# ECHO_RECEIVER.net
KiCad netlist of a schematic drawn in EasyEDA Pro
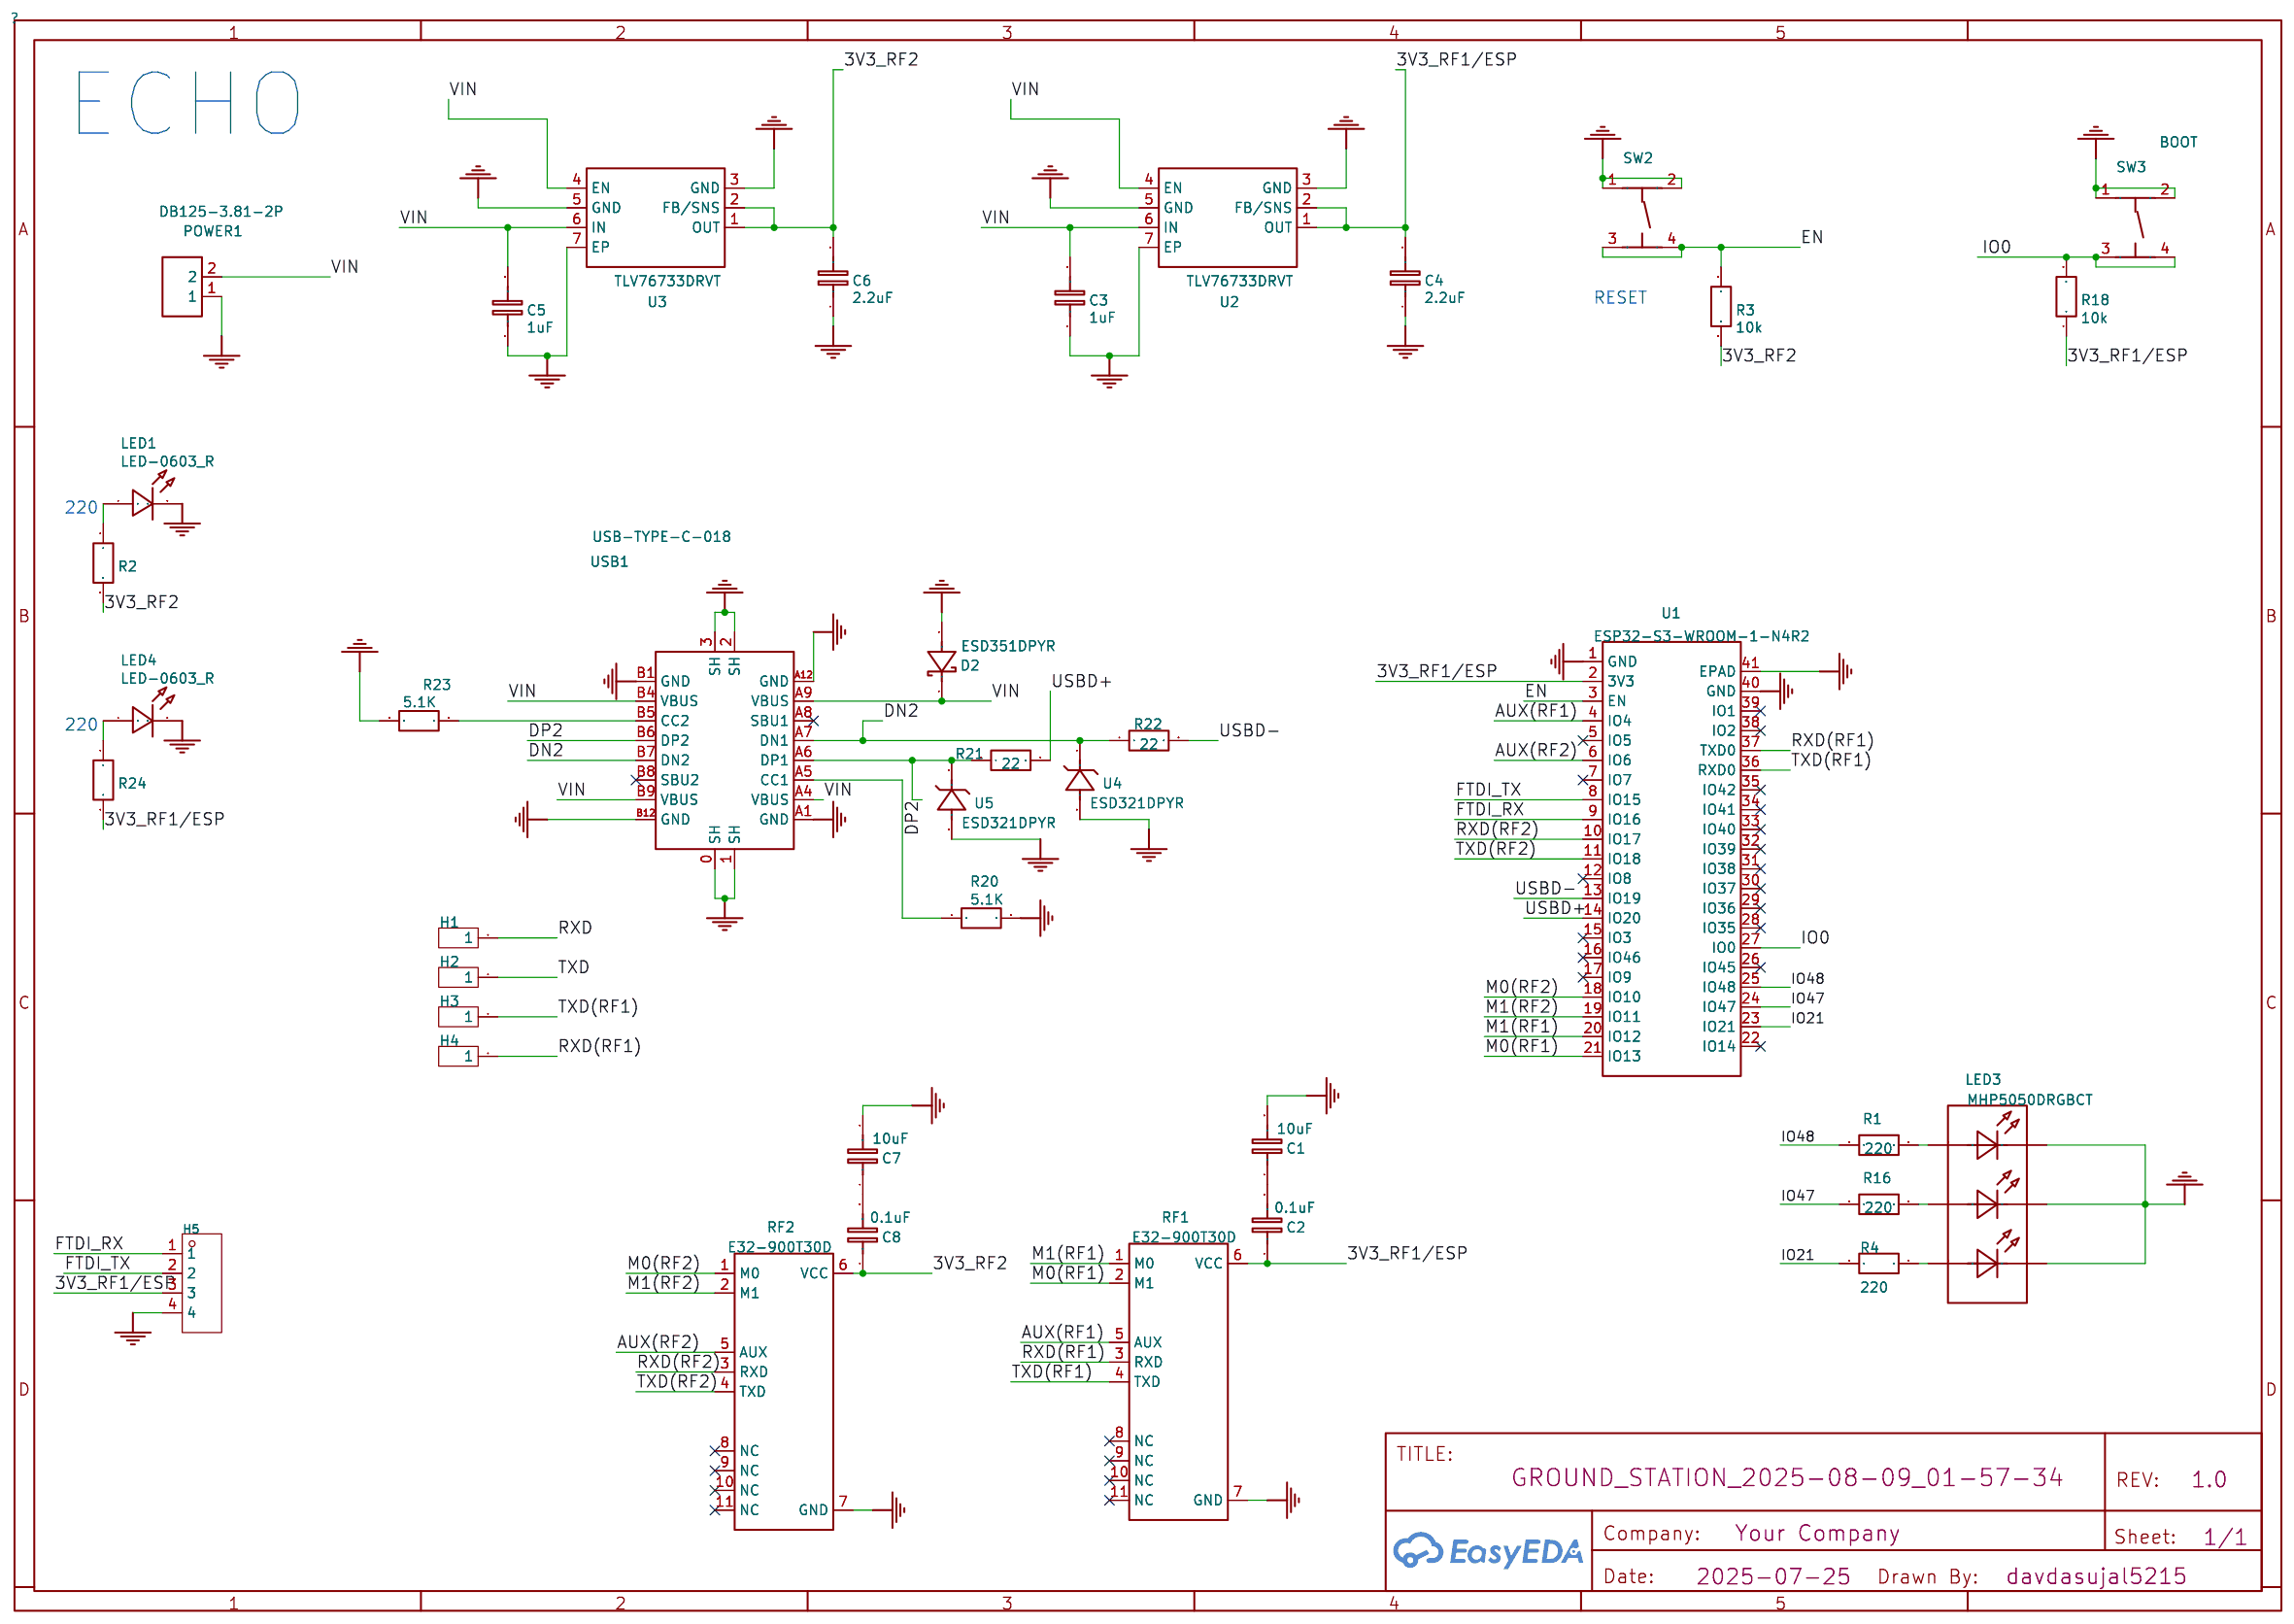
[diagram p0: schematic sheet]

(export (version "E")
  (design (tool "Eeschema 10.0.6"))
  (components
    (comp (ref "C1")
      (value "10uF")
      (footprint "easyedapro:C0603")
      (fields (field (name "Contributor") "LCEDA_Lib"))
      (libsource (lib "easyedapro") (part "10uF"))
    )
    (comp (ref "C2")
      (value "0.1uF")
      (footprint "easyedapro:C0603")
      (fields (field (name "Contributor") "LCEDA_Lib"))
      (libsource (lib "easyedapro") (part "0.1uF"))
    )
    (comp (ref "C3")
      (value "1uF")
      (footprint "easyedapro:C0603")
      (fields (field (name "Contributor") "LCEDA_Lib"))
      (libsource (lib "easyedapro") (part "1uF"))
    )
    (comp (ref "C4")
      (value "2.2uF")
      (footprint "easyedapro:C0603")
      (fields (field (name "Contributor") "LCEDA_Lib"))
      (libsource (lib "easyedapro") (part "2.2uF"))
    )
    (comp (ref "C5")
      (value "1uF")
      (footprint "easyedapro:C0603")
      (fields (field (name "Contributor") "LCEDA_Lib"))
      (libsource (lib "easyedapro") (part "1uF"))
    )
    (comp (ref "C6")
      (value "2.2uF")
      (footprint "easyedapro:C0603")
      (fields (field (name "Contributor") "LCEDA_Lib"))
      (libsource (lib "easyedapro") (part "2.2uF"))
    )
    (comp (ref "C7")
      (value "10uF")
      (footprint "easyedapro:C0603")
      (fields (field (name "Contributor") "LCEDA_Lib"))
      (libsource (lib "easyedapro") (part "10uF"))
    )
    (comp (ref "C8")
      (value "0.1uF")
      (footprint "easyedapro:C0603")
      (fields (field (name "Contributor") "LCEDA_Lib"))
      (libsource (lib "easyedapro") (part "0.1uF"))
    )
    (comp (ref "D2")
      (value "ESD351DPYR")
      (footprint "easyedapro:X1SON-2_L1.0-W0.6-P0.65-RD-1")
      (fields (field (name "Manufacturer") "TI(德州仪器)") (field (name "Contributor") "LCSC"))
      (libsource (lib "easyedapro") (part "ESD351DPYR"))
    )
    (comp (ref "H1")
      (value "~")
      (footprint "easyedapro:HDR-TH_1P-V-M_XKB_X4611WV-01I-C28D40")
      (libsource (lib "easyedapro") (part "HDR_1x1"))
    )
    (comp (ref "H2")
      (value "~")
      (footprint "easyedapro:HDR-TH_1P-V-M_XKB_X4611WV-01I-C28D40")
      (libsource (lib "easyedapro") (part "HDR_1x1"))
    )
    (comp (ref "H3")
      (value "~")
      (footprint "easyedapro:HDR-TH_1P-V-M_XKB_X4611WV-01I-C28D40")
      (libsource (lib "easyedapro") (part "HDR_1x1"))
    )
    (comp (ref "H4")
      (value "~")
      (footprint "easyedapro:HDR-TH_1P-V-M_XKB_X4611WV-01I-C28D40")
      (libsource (lib "easyedapro") (part "HDR_1x1"))
    )
    (comp (ref "H5")
      (value "~")
      (footprint "easyedapro:HDR-TH_4P-P2.54-V-F")
      (libsource (lib "easyedapro") (part "2.54-1*4P母"))
    )
    (comp (ref "LED1")
      (value "LED-0603_R")
      (footprint "easyedapro:LED0603_RED")
      (fields
        (field (name "Manufacturer Part") "19-217/R6C-AL1M2VY/3T")
        (field (name "Manufacturer") "EVERLIGHT(台湾亿光)")
        (field (name "Contributor") "LCEDA_01")
      )
      (libsource (lib "easyedapro") (part "LED-0603_R"))
    )
    (comp (ref "LED3")
      (value "MHP5050DRGBCT")
      (footprint "easyedapro:LED-SMD_6P-L5.0-W5.0-P1.60-LS4.4-TL_MHP5050DRGBCT")
      (fields (field (name "Manufacturer") "MEIHUA(美华)") (field (name "Contributor") "lcsc"))
      (libsource (lib "easyedapro") (part "MHP5050DRGBCT"))
    )
    (comp (ref "LED4")
      (value "LED-0603_R")
      (footprint "easyedapro:LED0603_RED")
      (fields
        (field (name "Manufacturer Part") "19-217/R6C-AL1M2VY/3T")
        (field (name "Manufacturer") "EVERLIGHT(台湾亿光)")
        (field (name "Contributor") "LCEDA_01")
      )
      (libsource (lib "easyedapro") (part "LED-0603_R"))
    )
    (comp (ref "POWER1")
      (value "DB125-3.81-2P")
      (footprint "easyedapro:CONN-TH_2P-P3.81_L7.4-W7.6")
      (fields
        (field (name "Manufacturer Part") "DB125-3.81-2P-GN-S")
        (field (name "Manufacturer") "DORABO(地博电气)")
        (field (name "Contributor") "LCSC")
      )
      (libsource (lib "easyedapro") (part "DB125-3.81-2P"))
    )
    (comp (ref "R1")
      (value "220")
      (footprint "easyedapro:R0603")
      (fields (field (name "Contributor") "LCEDA_Lib"))
      (libsource (lib "easyedapro") (part "220"))
    )
    (comp (ref "R2")
      (value "10k")
      (footprint "easyedapro:R0603")
      (fields (field (name "Contributor") "LCEDA_Lib"))
      (libsource (lib "easyedapro") (part "10k"))
    )
    (comp (ref "R3")
      (value "10k")
      (footprint "easyedapro:R0603")
      (fields (field (name "Contributor") "LCEDA_Lib"))
      (libsource (lib "easyedapro") (part "10k"))
    )
    (comp (ref "R4")
      (value "220")
      (footprint "easyedapro:R0603")
      (fields (field (name "Contributor") "LCEDA_Lib"))
      (libsource (lib "") (part "220_1"))
    )
    (comp (ref "R16")
      (value "220")
      (footprint "easyedapro:R0603")
      (fields (field (name "Contributor") "LCEDA_Lib"))
      (libsource (lib "easyedapro") (part "220"))
    )
    (comp (ref "R18")
      (value "10k")
      (footprint "easyedapro:R0603")
      (fields (field (name "Contributor") "LCEDA_Lib"))
      (libsource (lib "") (part "10k_1"))
    )
    (comp (ref "R20")
      (value "5.1K")
      (footprint "easyedapro:R0603")
      (fields (field (name "Contributor") "LCEDA_Lib"))
      (libsource (lib "easyedapro") (part "5.1K"))
    )
    (comp (ref "R21")
      (value "22")
      (footprint "easyedapro:R0603")
      (fields (field (name "Contributor") "LCEDA_Lib"))
      (libsource (lib "easyedapro") (part "22"))
    )
    (comp (ref "R22")
      (value "22")
      (footprint "easyedapro:R0603")
      (fields (field (name "Contributor") "LCEDA_Lib"))
      (libsource (lib "easyedapro") (part "22"))
    )
    (comp (ref "R23")
      (value "5.1K")
      (footprint "easyedapro:R0603")
      (fields (field (name "Contributor") "LCEDA_Lib"))
      (libsource (lib "") (part "5.1K_1"))
    )
    (comp (ref "R24")
      (value "10k")
      (footprint "easyedapro:R0603")
      (fields (field (name "Contributor") "LCEDA_Lib"))
      (libsource (lib "easyedapro") (part "10k"))
    )
    (comp (ref "RF1")
      (value "E32-900T30D")
      (footprint "easyedapro:WIRELM-TH_E32-900T30D")
      (fields (field (name "Contributor") "lcsc"))
      (libsource (lib "easyedapro") (part "E32-900T30D"))
    )
    (comp (ref "RF2")
      (value "E32-900T30D")
      (footprint "easyedapro:WIRELM-TH_E32-900T30D")
      (fields (field (name "Contributor") "lcsc"))
      (libsource (lib "easyedapro") (part "E32-900T30D"))
    )
    (comp (ref "SW2")
      (value "RESET")
      (footprint "easyedapro:SW-SMD_4P-L4.5-W4.5-P3.00-LS7.0")
      (fields
        (field (name "Manufacturer Part") "TS-1109S-C-A")
        (field (name "Manufacturer") "XKB Enterprise")
        (field (name "Contributor") "Igor Iks")
      )
      (libsource (lib "easyedapro") (part "RESET"))
    )
    (comp (ref "SW3")
      (value "BOOT")
      (footprint "easyedapro:SW-SMD_4P-L4.5-W4.5-P3.00-LS7.0")
      (fields
        (field (name "Manufacturer Part") "TS-1109S-C-A")
        (field (name "Manufacturer") "XKB Enterprise")
        (field (name "Contributor") "Igor Iks")
      )
      (libsource (lib "easyedapro") (part "BOOT"))
    )
    (comp (ref "U1")
      (value "ESP32-S3-WROOM-1-N4R2")
      (footprint "easyedapro:WIRELM-SMD_ESP32-S3-WROOM-1")
      (fields (field (name "Manufacturer") "ESPRESSIF(乐鑫)") (field (name "Contributor") "lcsc"))
      (libsource (lib "easyedapro") (part "ESP32-S3-WROOM-1-N4R2"))
    )
    (comp (ref "U2")
      (value "TLV76733DRVT")
      (footprint "easyedapro:WSON-6_L2.0-W2.0-P0.65-TL-EP")
      (fields (field (name "Manufacturer") "TI(德州仪器)") (field (name "Contributor") "LCSC"))
      (libsource (lib "easyedapro") (part "TLV76733DRVT"))
    )
    (comp (ref "U3")
      (value "TLV76733DRVT")
      (footprint "easyedapro:WSON-6_L2.0-W2.0-P0.65-TL-EP")
      (fields (field (name "Manufacturer") "TI(德州仪器)") (field (name "Contributor") "LCSC"))
      (libsource (lib "easyedapro") (part "TLV76733DRVT"))
    )
    (comp (ref "U4")
      (value "ESD321DPYR")
      (footprint "easyedapro:X1SON-2_L1.0-W0.6-P0.65-RD")
      (fields (field (name "Contributor") "LCSC"))
      (libsource (lib "easyedapro") (part "ESD321DPYR"))
    )
    (comp (ref "U5")
      (value "ESD321DPYR")
      (footprint "easyedapro:X1SON-2_L1.0-W0.6-P0.65-RD")
      (fields (field (name "Contributor") "LCSC"))
      (libsource (lib "easyedapro") (part "ESD321DPYR"))
    )
    (comp (ref "USB1")
      (value "USB-TYPE-C-018")
      (footprint "easyedapro:USB-C_SMD-TYPE-C-31-M-12")
      (fields (field (name "Manufacturer") "DEALON(德艺隆)") (field (name "Contributor") "LCSC"))
      (libsource (lib "easyedapro") (part "USB-TYPE-C-018"))
    )
  )
  (nets
    (net (code "1") (name "/3V3_RF1{slash}ESP") (class "Default")
      (node (ref "C2") (pin "1") (pinfunction "1_1") (pintype "unspecified"))
      (node (ref "C4") (pin "2") (pinfunction "2_2") (pintype "unspecified"))
      (node (ref "H5") (pin "3") (pinfunction "3_3") (pintype "input"))
      (node (ref "R18") (pin "1") (pinfunction "1_1") (pintype "unspecified"))
      (node (ref "R24") (pin "2") (pinfunction "2_2") (pintype "unspecified"))
      (node (ref "RF1") (pin "6") (pinfunction "VCC_6") (pintype "unspecified"))
      (node (ref "U1") (pin "2") (pinfunction "3V3_2") (pintype "unspecified"))
      (node (ref "U2") (pin "1") (pinfunction "OUT_1") (pintype "unspecified"))
      (node (ref "U2") (pin "2") (pinfunction "FB/SNS_2") (pintype "unspecified"))
    )
    (net (code "2") (name "/3V3_RF2") (class "Default")
      (node (ref "C6") (pin "2") (pinfunction "2_2") (pintype "unspecified"))
      (node (ref "C8") (pin "1") (pinfunction "1_1") (pintype "unspecified"))
      (node (ref "R2") (pin "2") (pinfunction "2_2") (pintype "unspecified"))
      (node (ref "R3") (pin "2") (pinfunction "2_2") (pintype "unspecified"))
      (node (ref "RF2") (pin "6") (pinfunction "VCC_6") (pintype "unspecified"))
      (node (ref "U3") (pin "1") (pinfunction "OUT_1") (pintype "unspecified"))
      (node (ref "U3") (pin "2") (pinfunction "FB/SNS_2") (pintype "unspecified"))
    )
    (net (code "3") (name "/AUX(RF1)") (class "Default")
      (node (ref "RF1") (pin "5") (pinfunction "AUX_5") (pintype "unspecified"))
      (node (ref "U1") (pin "4") (pinfunction "IO4_4") (pintype "unspecified"))
    )
    (net (code "4") (name "/AUX(RF2)") (class "Default")
      (node (ref "RF2") (pin "5") (pinfunction "AUX_5") (pintype "unspecified"))
      (node (ref "U1") (pin "6") (pinfunction "IO6_6") (pintype "unspecified"))
    )
    (net (code "5") (name "/DN2") (class "Default")
      (node (ref "R22") (pin "1") (pinfunction "1_1") (pintype "unspecified"))
      (node (ref "U4") (pin "1") (pinfunction "K_1") (pintype "unspecified"))
      (node (ref "USB1") (pin "A7") (pinfunction "DN1_A7") (pintype "unspecified"))
      (node (ref "USB1") (pin "B7") (pinfunction "DN2_B7") (pintype "unspecified"))
    )
    (net (code "6") (name "/DP2") (class "Default")
      (node (ref "R21") (pin "1") (pinfunction "1_1") (pintype "unspecified"))
      (node (ref "U5") (pin "1") (pinfunction "K_1") (pintype "unspecified"))
      (node (ref "USB1") (pin "A6") (pinfunction "DP1_A6") (pintype "unspecified"))
      (node (ref "USB1") (pin "B6") (pinfunction "DP2_B6") (pintype "unspecified"))
    )
    (net (code "7") (name "/EN") (class "Default")
      (node (ref "R3") (pin "1") (pinfunction "1_1") (pintype "unspecified"))
      (node (ref "SW2") (pin "3") (pinfunction "3_3") (pintype "unspecified"))
      (node (ref "SW2") (pin "4") (pinfunction "4_4") (pintype "unspecified"))
      (node (ref "U1") (pin "3") (pinfunction "EN_3") (pintype "unspecified"))
    )
    (net (code "8") (name "/FTDI_RX") (class "Default")
      (node (ref "H5") (pin "1") (pinfunction "1_1") (pintype "input"))
      (node (ref "U1") (pin "9") (pinfunction "IO16_9") (pintype "unspecified"))
    )
    (net (code "9") (name "/FTDI_TX") (class "Default")
      (node (ref "H5") (pin "2") (pinfunction "2_2") (pintype "input"))
      (node (ref "U1") (pin "8") (pinfunction "IO15_8") (pintype "unspecified"))
    )
    (net (code "10") (name "/IO0") (class "Default")
      (node (ref "R18") (pin "2") (pinfunction "2_2") (pintype "unspecified"))
      (node (ref "SW3") (pin "3") (pinfunction "3_3") (pintype "unspecified"))
      (node (ref "SW3") (pin "4") (pinfunction "4_4") (pintype "unspecified"))
      (node (ref "U1") (pin "27") (pinfunction "IO0_27") (pintype "unspecified"))
    )
    (net (code "11") (name "/IO21") (class "Default")
      (node (ref "R4") (pin "2") (pinfunction "2_2") (pintype "unspecified"))
      (node (ref "U1") (pin "23") (pinfunction "IO21_23") (pintype "unspecified"))
    )
    (net (code "12") (name "/IO47") (class "Default")
      (node (ref "R16") (pin "1") (pinfunction "1_1") (pintype "unspecified"))
      (node (ref "U1") (pin "24") (pinfunction "IO47_24") (pintype "unspecified"))
    )
    (net (code "13") (name "/IO48") (class "Default")
      (node (ref "R1") (pin "1") (pinfunction "1_1") (pintype "unspecified"))
      (node (ref "U1") (pin "25") (pinfunction "IO48_25") (pintype "unspecified"))
    )
    (net (code "14") (name "/M0(RF1)") (class "Default")
      (node (ref "RF1") (pin "2") (pinfunction "M1_2") (pintype "unspecified"))
      (node (ref "U1") (pin "21") (pinfunction "IO13_21") (pintype "unspecified"))
    )
    (net (code "15") (name "/M0(RF2)") (class "Default")
      (node (ref "RF2") (pin "1") (pinfunction "M0_1") (pintype "unspecified"))
      (node (ref "U1") (pin "18") (pinfunction "IO10_18") (pintype "unspecified"))
    )
    (net (code "16") (name "/M1(RF1)") (class "Default")
      (node (ref "RF1") (pin "1") (pinfunction "M0_1") (pintype "unspecified"))
      (node (ref "U1") (pin "20") (pinfunction "IO12_20") (pintype "unspecified"))
    )
    (net (code "17") (name "/M1(RF2)") (class "Default")
      (node (ref "RF2") (pin "2") (pinfunction "M1_2") (pintype "unspecified"))
      (node (ref "U1") (pin "19") (pinfunction "IO11_19") (pintype "unspecified"))
    )
    (net (code "18") (name "/RXD") (class "Default")
      (node (ref "H1") (pin "1") (pinfunction "1_1") (pintype "unspecified"))
    )
    (net (code "19") (name "/RXD(RF1)") (class "Default")
      (node (ref "H4") (pin "1") (pinfunction "1_1") (pintype "unspecified"))
      (node (ref "RF1") (pin "3") (pinfunction "RXD_3") (pintype "unspecified"))
      (node (ref "U1") (pin "37") (pinfunction "TXD0_37") (pintype "unspecified"))
    )
    (net (code "20") (name "/RXD(RF2)") (class "Default")
      (node (ref "RF2") (pin "3") (pinfunction "RXD_3") (pintype "unspecified"))
      (node (ref "U1") (pin "10") (pinfunction "IO17_10") (pintype "unspecified"))
    )
    (net (code "21") (name "/TXD") (class "Default")
      (node (ref "H2") (pin "1") (pinfunction "1_1") (pintype "unspecified"))
    )
    (net (code "22") (name "/TXD(RF1)") (class "Default")
      (node (ref "H3") (pin "1") (pinfunction "1_1") (pintype "unspecified"))
      (node (ref "RF1") (pin "4") (pinfunction "TXD_4") (pintype "unspecified"))
      (node (ref "U1") (pin "36") (pinfunction "RXD0_36") (pintype "unspecified"))
    )
    (net (code "23") (name "/TXD(RF2)") (class "Default")
      (node (ref "RF2") (pin "4") (pinfunction "TXD_4") (pintype "unspecified"))
      (node (ref "U1") (pin "11") (pinfunction "IO18_11") (pintype "unspecified"))
    )
    (net (code "24") (name "/USBD+") (class "Default")
      (node (ref "R21") (pin "2") (pinfunction "2_2") (pintype "unspecified"))
      (node (ref "U1") (pin "14") (pinfunction "IO20_14") (pintype "unspecified"))
    )
    (net (code "25") (name "/USBD-") (class "Default")
      (node (ref "R22") (pin "2") (pinfunction "2_2") (pintype "unspecified"))
      (node (ref "U1") (pin "13") (pinfunction "IO19_13") (pintype "unspecified"))
    )
    (net (code "26") (name "/VIN") (class "Default")
      (node (ref "C3") (pin "2") (pinfunction "2_2") (pintype "unspecified"))
      (node (ref "C5") (pin "2") (pinfunction "2_2") (pintype "unspecified"))
      (node (ref "D2") (pin "1") (pinfunction "K_1") (pintype "unspecified"))
      (node (ref "POWER1") (pin "2") (pinfunction "2_2") (pintype "unspecified"))
      (node (ref "U2") (pin "4") (pinfunction "EN_4") (pintype "unspecified"))
      (node (ref "U2") (pin "6") (pinfunction "IN_6") (pintype "unspecified"))
      (node (ref "U3") (pin "4") (pinfunction "EN_4") (pintype "unspecified"))
      (node (ref "U3") (pin "6") (pinfunction "IN_6") (pintype "unspecified"))
      (node (ref "USB1") (pin "A4") (pinfunction "VBUS_A4") (pintype "unspecified"))
      (node (ref "USB1") (pin "A9") (pinfunction "VBUS_A9") (pintype "unspecified"))
      (node (ref "USB1") (pin "B4") (pinfunction "VBUS_B4") (pintype "unspecified"))
      (node (ref "USB1") (pin "B9") (pinfunction "VBUS_B9") (pintype "unspecified"))
    )
    (net (code "27") (name "GND") (class "Default")
      (node (ref "C1") (pin "2") (pinfunction "2_2") (pintype "unspecified"))
      (node (ref "C3") (pin "1") (pinfunction "1_1") (pintype "unspecified"))
      (node (ref "C4") (pin "1") (pinfunction "1_1") (pintype "unspecified"))
      (node (ref "C5") (pin "1") (pinfunction "1_1") (pintype "unspecified"))
      (node (ref "C6") (pin "1") (pinfunction "1_1") (pintype "unspecified"))
      (node (ref "C7") (pin "2") (pinfunction "2_2") (pintype "unspecified"))
      (node (ref "D2") (pin "2") (pinfunction "A_2") (pintype "unspecified"))
      (node (ref "H5") (pin "4") (pinfunction "4_4") (pintype "input"))
      (node (ref "LED1") (pin "2") (pinfunction "2_2") (pintype "unspecified"))
      (node (ref "LED3") (pin "4") (pinfunction "B-_4") (pintype "unspecified"))
      (node (ref "LED3") (pin "5") (pinfunction "R-_5") (pintype "unspecified"))
      (node (ref "LED3") (pin "6") (pinfunction "G-_6") (pintype "unspecified"))
      (node (ref "LED4") (pin "2") (pinfunction "2_2") (pintype "unspecified"))
      (node (ref "POWER1") (pin "1") (pinfunction "1_1") (pintype "unspecified"))
      (node (ref "R20") (pin "2") (pinfunction "2_2") (pintype "unspecified"))
      (node (ref "R23") (pin "2") (pinfunction "2_2") (pintype "unspecified"))
      (node (ref "RF1") (pin "7") (pinfunction "GND_7") (pintype "unspecified"))
      (node (ref "RF2") (pin "7") (pinfunction "GND_7") (pintype "unspecified"))
      (node (ref "SW2") (pin "1") (pinfunction "1_1") (pintype "unspecified"))
      (node (ref "SW2") (pin "2") (pinfunction "2_2") (pintype "unspecified"))
      (node (ref "SW3") (pin "1") (pinfunction "1_1") (pintype "unspecified"))
      (node (ref "SW3") (pin "2") (pinfunction "2_2") (pintype "unspecified"))
      (node (ref "U1") (pin "1") (pinfunction "GND_1") (pintype "unspecified"))
      (node (ref "U1") (pin "40") (pinfunction "GND_40") (pintype "unspecified"))
      (node (ref "U1") (pin "41") (pinfunction "EPAD_41") (pintype "unspecified"))
      (node (ref "U2") (pin "3") (pinfunction "GND_3") (pintype "unspecified"))
      (node (ref "U2") (pin "5") (pinfunction "GND_5") (pintype "unspecified"))
      (node (ref "U2") (pin "7") (pinfunction "EP_7") (pintype "unspecified"))
      (node (ref "U3") (pin "3") (pinfunction "GND_3") (pintype "unspecified"))
      (node (ref "U3") (pin "5") (pinfunction "GND_5") (pintype "unspecified"))
      (node (ref "U3") (pin "7") (pinfunction "EP_7") (pintype "unspecified"))
      (node (ref "U4") (pin "2") (pinfunction "A_2") (pintype "unspecified"))
      (node (ref "U5") (pin "2") (pinfunction "A_2") (pintype "unspecified"))
      (node (ref "USB1") (pin "0") (pinfunction "SH_0") (pintype "unspecified"))
      (node (ref "USB1") (pin "1") (pinfunction "SH_1") (pintype "unspecified"))
      (node (ref "USB1") (pin "2") (pinfunction "SH_2") (pintype "unspecified"))
      (node (ref "USB1") (pin "3") (pinfunction "SH_3") (pintype "unspecified"))
      (node (ref "USB1") (pin "A1") (pinfunction "GND_A1") (pintype "unspecified"))
      (node (ref "USB1") (pin "A12") (pinfunction "GND_A12") (pintype "unspecified"))
      (node (ref "USB1") (pin "B1") (pinfunction "GND_B1") (pintype "unspecified"))
      (node (ref "USB1") (pin "B12") (pinfunction "GND_B12") (pintype "unspecified"))
    )
    (net (code "28") (name "Net-(C1-Pad1)") (class "Default")
      (node (ref "C1") (pin "1") (pinfunction "1_1") (pintype "unspecified"))
      (node (ref "C2") (pin "2") (pinfunction "2_2") (pintype "unspecified"))
    )
    (net (code "29") (name "Net-(C7-Pad1)") (class "Default")
      (node (ref "C7") (pin "1") (pinfunction "1_1") (pintype "unspecified"))
      (node (ref "C8") (pin "2") (pinfunction "2_2") (pintype "unspecified"))
    )
    (net (code "30") (name "Net-(LED1-Pad1)") (class "Default")
      (node (ref "LED1") (pin "1") (pinfunction "1_1") (pintype "unspecified"))
      (node (ref "R2") (pin "1") (pinfunction "1_1") (pintype "unspecified"))
    )
    (net (code "31") (name "Net-(LED3-B+)") (class "Default")
      (node (ref "LED3") (pin "3") (pinfunction "B+_3") (pintype "unspecified"))
      (node (ref "R4") (pin "1") (pinfunction "1_1") (pintype "unspecified"))
    )
    (net (code "32") (name "Net-(LED3-G+)") (class "Default")
      (node (ref "LED3") (pin "1") (pinfunction "G+_1") (pintype "unspecified"))
      (node (ref "R1") (pin "2") (pinfunction "2_2") (pintype "unspecified"))
    )
    (net (code "33") (name "Net-(LED3-R+)") (class "Default")
      (node (ref "LED3") (pin "2") (pinfunction "R+_2") (pintype "unspecified"))
      (node (ref "R16") (pin "2") (pinfunction "2_2") (pintype "unspecified"))
    )
    (net (code "34") (name "Net-(LED4-Pad1)") (class "Default")
      (node (ref "LED4") (pin "1") (pinfunction "1_1") (pintype "unspecified"))
      (node (ref "R24") (pin "1") (pinfunction "1_1") (pintype "unspecified"))
    )
    (net (code "35") (name "Net-(USB1-CC1)") (class "Default")
      (node (ref "R20") (pin "1") (pinfunction "1_1") (pintype "unspecified"))
      (node (ref "USB1") (pin "A5") (pinfunction "CC1_A5") (pintype "unspecified"))
    )
    (net (code "36") (name "Net-(USB1-CC2)") (class "Default")
      (node (ref "R23") (pin "1") (pinfunction "1_1") (pintype "unspecified"))
      (node (ref "USB1") (pin "B5") (pinfunction "CC2_B5") (pintype "unspecified"))
    )
    (net (code "37") (name "unconnected-(RF1-NC-Pad8)") (class "Default")
      (node (ref "RF1") (pin "8") (pinfunction "NC_8") (pintype "unspecified+no_connect"))
    )
    (net (code "38") (name "unconnected-(RF1-NC-Pad9)") (class "Default")
      (node (ref "RF1") (pin "9") (pinfunction "NC_9") (pintype "unspecified+no_connect"))
    )
    (net (code "39") (name "unconnected-(RF1-NC-Pad10)") (class "Default")
      (node (ref "RF1") (pin "10") (pinfunction "NC_10") (pintype "unspecified+no_connect"))
    )
    (net (code "40") (name "unconnected-(RF1-NC-Pad11)") (class "Default")
      (node (ref "RF1") (pin "11") (pinfunction "NC_11") (pintype "unspecified+no_connect"))
    )
    (net (code "41") (name "unconnected-(RF2-NC-Pad8)") (class "Default")
      (node (ref "RF2") (pin "8") (pinfunction "NC_8") (pintype "unspecified+no_connect"))
    )
    (net (code "42") (name "unconnected-(RF2-NC-Pad9)") (class "Default")
      (node (ref "RF2") (pin "9") (pinfunction "NC_9") (pintype "unspecified+no_connect"))
    )
    (net (code "43") (name "unconnected-(RF2-NC-Pad10)") (class "Default")
      (node (ref "RF2") (pin "10") (pinfunction "NC_10") (pintype "unspecified+no_connect"))
    )
    (net (code "44") (name "unconnected-(RF2-NC-Pad11)") (class "Default")
      (node (ref "RF2") (pin "11") (pinfunction "NC_11") (pintype "unspecified+no_connect"))
    )
    (net (code "45") (name "unconnected-(U1-IO1-Pad39)") (class "Default")
      (node (ref "U1") (pin "39") (pinfunction "IO1_39") (pintype "unspecified+no_connect"))
    )
    (net (code "46") (name "unconnected-(U1-IO2-Pad38)") (class "Default")
      (node (ref "U1") (pin "38") (pinfunction "IO2_38") (pintype "unspecified+no_connect"))
    )
    (net (code "47") (name "unconnected-(U1-IO3-Pad15)") (class "Default")
      (node (ref "U1") (pin "15") (pinfunction "IO3_15") (pintype "unspecified+no_connect"))
    )
    (net (code "48") (name "unconnected-(U1-IO5-Pad5)") (class "Default")
      (node (ref "U1") (pin "5") (pinfunction "IO5_5") (pintype "unspecified+no_connect"))
    )
    (net (code "49") (name "unconnected-(U1-IO7-Pad7)") (class "Default")
      (node (ref "U1") (pin "7") (pinfunction "IO7_7") (pintype "unspecified+no_connect"))
    )
    (net (code "50") (name "unconnected-(U1-IO8-Pad12)") (class "Default")
      (node (ref "U1") (pin "12") (pinfunction "IO8_12") (pintype "unspecified+no_connect"))
    )
    (net (code "51") (name "unconnected-(U1-IO9-Pad17)") (class "Default")
      (node (ref "U1") (pin "17") (pinfunction "IO9_17") (pintype "unspecified+no_connect"))
    )
    (net (code "52") (name "unconnected-(U1-IO14-Pad22)") (class "Default")
      (node (ref "U1") (pin "22") (pinfunction "IO14_22") (pintype "unspecified+no_connect"))
    )
    (net (code "53") (name "unconnected-(U1-IO35-Pad28)") (class "Default")
      (node (ref "U1") (pin "28") (pinfunction "IO35_28") (pintype "unspecified+no_connect"))
    )
    (net (code "54") (name "unconnected-(U1-IO36-Pad29)") (class "Default")
      (node (ref "U1") (pin "29") (pinfunction "IO36_29") (pintype "unspecified+no_connect"))
    )
    (net (code "55") (name "unconnected-(U1-IO37-Pad30)") (class "Default")
      (node (ref "U1") (pin "30") (pinfunction "IO37_30") (pintype "unspecified+no_connect"))
    )
    (net (code "56") (name "unconnected-(U1-IO38-Pad31)") (class "Default")
      (node (ref "U1") (pin "31") (pinfunction "IO38_31") (pintype "unspecified+no_connect"))
    )
    (net (code "57") (name "unconnected-(U1-IO39-Pad32)") (class "Default")
      (node (ref "U1") (pin "32") (pinfunction "IO39_32") (pintype "unspecified+no_connect"))
    )
    (net (code "58") (name "unconnected-(U1-IO40-Pad33)") (class "Default")
      (node (ref "U1") (pin "33") (pinfunction "IO40_33") (pintype "unspecified+no_connect"))
    )
    (net (code "59") (name "unconnected-(U1-IO41-Pad34)") (class "Default")
      (node (ref "U1") (pin "34") (pinfunction "IO41_34") (pintype "unspecified+no_connect"))
    )
    (net (code "60") (name "unconnected-(U1-IO42-Pad35)") (class "Default")
      (node (ref "U1") (pin "35") (pinfunction "IO42_35") (pintype "unspecified+no_connect"))
    )
    (net (code "61") (name "unconnected-(U1-IO45-Pad26)") (class "Default")
      (node (ref "U1") (pin "26") (pinfunction "IO45_26") (pintype "unspecified+no_connect"))
    )
    (net (code "62") (name "unconnected-(U1-IO46-Pad16)") (class "Default")
      (node (ref "U1") (pin "16") (pinfunction "IO46_16") (pintype "unspecified+no_connect"))
    )
    (net (code "63") (name "unconnected-(USB1-SBU1-PadA8)") (class "Default")
      (node (ref "USB1") (pin "A8") (pinfunction "SBU1_A8") (pintype "unspecified+no_connect"))
    )
    (net (code "64") (name "unconnected-(USB1-SBU2-PadB8)") (class "Default")
      (node (ref "USB1") (pin "B8") (pinfunction "SBU2_B8") (pintype "unspecified+no_connect"))
    )
  )
)
